# main_sch.net
KiCad netlist of a schematic drawn in Altium Designer
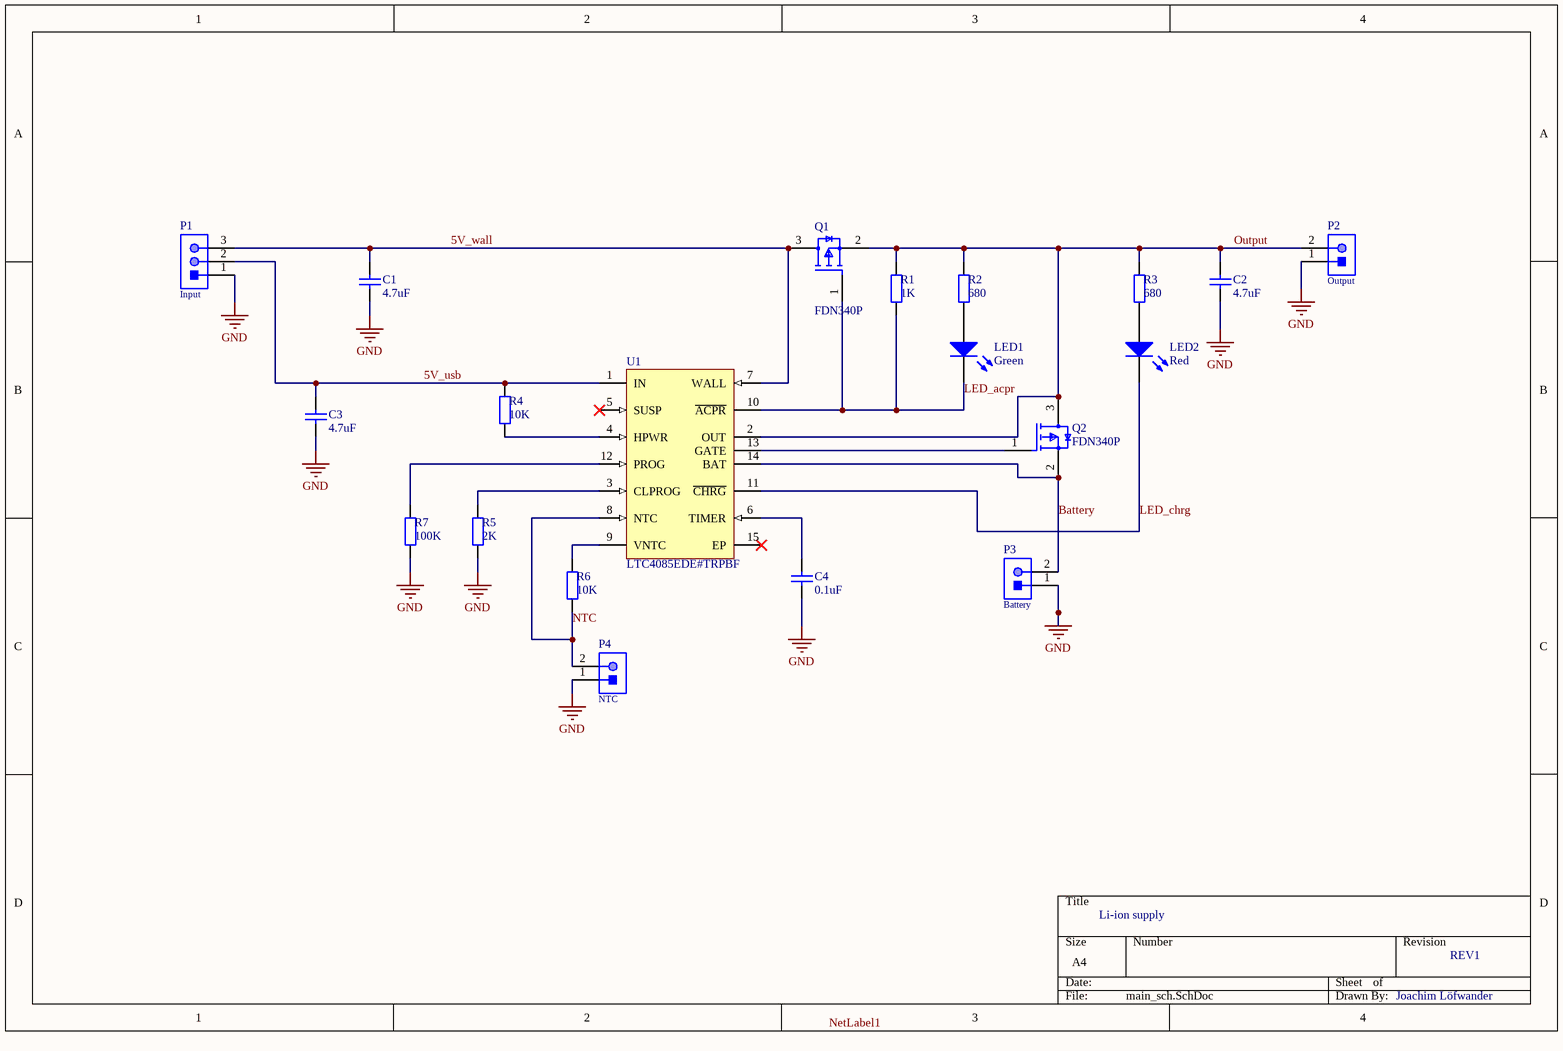
[diagram p0: main_sch.SchDoc]

(export (version "E")
  (design (tool "Eeschema 10.0.6"))
  (components
    (comp (ref "C1")
      (value "4.7uF")
      (footprint "CAPC2013X145X50ML20T25")
      (fields (field (name "MANUFACTURER") "Kemet") (field (name "PART NUMBER") "C0805C475K3PACTU"))
      (libsource (lib "Altium Content Vault") (part "CAP"))
    )
    (comp (ref "C2")
      (value "4.7uF")
      (footprint "CAPC2013X145X50ML20T25")
      (fields (field (name "MANUFACTURER") "Kemet") (field (name "PART NUMBER") "C0805C475K3PACTU"))
      (libsource (lib "Altium Content Vault") (part "CAP"))
    )
    (comp (ref "C3")
      (value "4.7uF")
      (footprint "CAPC2013X145X50ML20T25")
      (fields (field (name "MANUFACTURER") "Kemet") (field (name "PART NUMBER") "C0805C475K3PACTU"))
      (libsource (lib "Altium Content Vault") (part "CAP"))
    )
    (comp (ref "C4")
      (value "0.1uF")
      (footprint "CAPC2013X135X45ML10T25")
      (description "Chip Capacitor, 0.1 uF, +/- 10%, 50 V, -55 to 125 degC, 0805 (2012 Metric), RoHS, Tape and Reel")
      (fields (field (name "VOLTAGE") "50V") (field (name "TOLERANCE") "10%"))
      (libsource (lib "Altium Content Vault") (part "CAP-NP-2"))
    )
    (comp (ref "LED1")
      (value "Green")
      (footprint "0805_A")
      (description "SMD mono-color Chip LED, WL-SMCW, Green")
      (fields (field (name "PARTNUMBER") "150080GS75000") (field (name "MANUFACTURER") "Wuerth Elektronik"))
      (libsource (lib "Altium Content Vault") (part "WE-LED_K1A2-2"))
    )
    (comp (ref "LED2")
      (value "Red")
      (footprint "0805_A")
      (description "SMD mono-color Chip LED, WL-SMCW, Red")
      (fields (field (name "PARTNUMBER") "150080RS75000") (field (name "MANUFACTURER") "Wuerth Elektronik"))
      (libsource (lib "Altium Content Vault") (part "WE-LED_K1A2-2"))
    )
    (comp (ref "P1")
      (value "Input")
      (footprint "61300311121")
      (description "THT Vertical Pin Header WR-PHD, Pitch 2.54 mm, Single Row, 3 pins")
      (fields
        (field (name "PART NUMBER") "61300311121")
        (field (name "MANUFACTURER") "Wurth Elektronik")
        (field (name "PUBLISHER") "WurthElektronik")
      )
      (libsource (lib "Altium Content Vault") (part "WE-CN-1P-M-R3"))
    )
    (comp (ref "P2")
      (value "Output")
      (footprint "61300211121")
      (description "THT Vertical Pin Header WR-PHD, Pitch 2.54 mm, Single Row, 2 pins")
      (fields
        (field (name "MANUFACTURER") "Wurth Elektronik")
        (field (name "PART NUMBER") "61300211121")
        (field (name "PUBLISHER") "WurthElektronik")
      )
      (libsource (lib "") (part "WE-CN-1P-M-R2_1"))
    )
    (comp (ref "P3")
      (value "Battery")
      (footprint "61300211121")
      (description "THT Vertical Pin Header WR-PHD, Pitch 2.54 mm, Single Row, 2 pins")
      (fields
        (field (name "MANUFACTURER") "Wurth Elektronik")
        (field (name "PART NUMBER") "61300211121")
        (field (name "PUBLISHER") "WurthElektronik")
      )
      (libsource (lib "Altium Content Vault") (part "WE-CN-1P-M-R2"))
    )
    (comp (ref "P4")
      (value "NTC")
      (footprint "61300211121")
      (description "THT Vertical Pin Header WR-PHD, Pitch 2.54 mm, Single Row, 2 pins")
      (fields
        (field (name "MANUFACTURER") "Wurth Elektronik")
        (field (name "PART NUMBER") "61300211121")
        (field (name "PUBLISHER") "WurthElektronik")
      )
      (libsource (lib "") (part "WE-CN-1P-M-R2_1"))
    )
    (comp (ref "Q1")
      (value "FDN340P")
      (footprint "FP-527AG-MFG")
      (description "MOSFET P-CH 20V 2A SSOT3")
      (libsource (lib "Altium Content Vault") (part "d23f43cc42f60b967b7caccf14518fd"))
    )
    (comp (ref "Q2")
      (value "FDN340P")
      (footprint "FP-527AG-MFG")
      (description "MOSFET P-CH 20V 2A SSOT3")
      (libsource (lib "Altium Content Vault") (part "d23f43cc42f60b967b7caccf14518fd"))
    )
    (comp (ref "R1")
      (value "1K")
      (footprint "RESC2013X50X30ML20T20")
      (fields (field (name "PART NUMBER") "CRCW08051K00FKEA") (field (name "MANUFACTURER") "Vishay Dale"))
      (libsource (lib "Altium Content Vault") (part "RES"))
    )
    (comp (ref "R2")
      (value "680")
      (footprint "RESC2013X50X30ML20T20")
      (fields (field (name "MANUFACTURER") "Vishay Dale") (field (name "PART NUMBER") "CRCW0805680RFKEA"))
      (libsource (lib "Altium Content Vault") (part "RES"))
    )
    (comp (ref "R3")
      (value "680")
      (footprint "RESC2013X50X30ML20T20")
      (fields (field (name "MANUFACTURER") "Vishay Dale") (field (name "PART NUMBER") "CRCW0805680RFKEA"))
      (libsource (lib "Altium Content Vault") (part "RES"))
    )
    (comp (ref "R4")
      (value "10K")
      (footprint "RESC2013X70X40ML20T20")
      (fields (field (name "PART NUMBER") "ERJ-6GEYJ103V") (field (name "MANUFACTURER") "Panasonic"))
      (libsource (lib "Altium Content Vault") (part "RES"))
    )
    (comp (ref "R5")
      (value "2K")
      (footprint "RESC2013X60X35ML10T20")
      (fields (field (name "MANUFACTURER") "Yageo") (field (name "PART NUMBER") "RC0805JR-072KL"))
      (libsource (lib "Altium Content Vault") (part "RES"))
    )
    (comp (ref "R6")
      (value "10K")
      (footprint "RESC2012X145X30ML20T15")
      (fields (field (name "MANUFACTURER") "Vishay Dale") (field (name "PART NUMBER") "NTHS0805N02N1002JE"))
      (libsource (lib "Altium Content Vault") (part "RES"))
    )
    (comp (ref "R7")
      (value "100K")
      (footprint "RESC2013X70X40ML20T20")
      (fields (field (name "PART NUMBER") "ERJ-6GEYJ104V") (field (name "MANUFACTURER") "Panasonic"))
      (libsource (lib "Altium Content Vault") (part "RES"))
    )
    (comp (ref "U1")
      (value "LTC4085EDE#TRPBF")
      (footprint "LT-DE-14_V")
      (fields (field (name "MANUFACTURER") "Linear Technology"))
      (libsource (lib "Altium Content Vault") (part "LT-LTC4085-DE-14"))
    )
  )
  (nets
    (net (code "1") (name "/5V_usb") (class "Default")
      (node (ref "C3") (pin "2") (pinfunction "2_2") (pintype "passive"))
      (node (ref "P1") (pin "2") (pinfunction "2_2") (pintype "passive"))
      (node (ref "R4") (pin "2") (pinfunction "2_2") (pintype "passive"))
      (node (ref "U1") (pin "1") (pinfunction "IN_1") (pintype "power_in"))
    )
    (net (code "2") (name "/5V_wall") (class "Default")
      (node (ref "C1") (pin "2") (pinfunction "2_2") (pintype "passive"))
      (node (ref "P1") (pin "3") (pinfunction "3_3") (pintype "passive"))
      (node (ref "Q1") (pin "3") (pinfunction "D_3") (pintype "passive"))
      (node (ref "U1") (pin "7") (pinfunction "WALL_7") (pintype "input"))
    )
    (net (code "3") (name "/Battery") (class "Default")
      (node (ref "P3") (pin "2") (pinfunction "2_2") (pintype "passive"))
      (node (ref "Q2") (pin "2") (pinfunction "S_2") (pintype "passive"))
      (node (ref "U1") (pin "14") (pinfunction "BAT_14") (pintype "power_in"))
    )
    (net (code "4") (name "/LED_acpr") (class "Default")
      (node (ref "LED1") (pin "1") (pinfunction "K_1") (pintype "passive"))
      (node (ref "Q1") (pin "1") (pinfunction "G_1") (pintype "passive"))
      (node (ref "R1") (pin "1") (pinfunction "1_1") (pintype "passive"))
      (node (ref "U1") (pin "10") (pinfunction "~{ACPR}_10") (pintype "tri_state"))
    )
    (net (code "5") (name "/LED_chrg") (class "Default")
      (node (ref "LED2") (pin "1") (pinfunction "K_1") (pintype "passive"))
      (node (ref "U1") (pin "11") (pinfunction "~{CHRG}_11") (pintype "tri_state"))
    )
    (net (code "6") (name "/NTC") (class "Default")
      (node (ref "P4") (pin "2") (pinfunction "2_2") (pintype "passive"))
      (node (ref "R6") (pin "1") (pinfunction "1_1") (pintype "passive"))
      (node (ref "U1") (pin "8") (pinfunction "NTC_8") (pintype "input"))
    )
    (net (code "8") (name "/Output") (class "Default")
      (node (ref "C2") (pin "2") (pinfunction "2_2") (pintype "passive"))
      (node (ref "P2") (pin "2") (pinfunction "2_2") (pintype "passive"))
      (node (ref "Q1") (pin "2") (pinfunction "S_2") (pintype "passive"))
      (node (ref "Q2") (pin "3") (pinfunction "D_3") (pintype "passive"))
      (node (ref "R1") (pin "2") (pinfunction "2_2") (pintype "passive"))
      (node (ref "R2") (pin "2") (pinfunction "2_2") (pintype "passive"))
      (node (ref "R3") (pin "2") (pinfunction "2_2") (pintype "passive"))
      (node (ref "U1") (pin "2") (pinfunction "OUT_2") (pintype "power_in"))
    )
    (net (code "9") (name "GND") (class "Default")
      (node (ref "C1") (pin "1") (pinfunction "1_1") (pintype "passive"))
      (node (ref "C2") (pin "1") (pinfunction "1_1") (pintype "passive"))
      (node (ref "C3") (pin "1") (pinfunction "1_1") (pintype "passive"))
      (node (ref "C4") (pin "1") (pinfunction "1_1") (pintype "passive"))
      (node (ref "P1") (pin "1") (pinfunction "1_1") (pintype "passive"))
      (node (ref "P2") (pin "1") (pinfunction "1_1") (pintype "passive"))
      (node (ref "P3") (pin "1") (pinfunction "1_1") (pintype "passive"))
      (node (ref "P4") (pin "1") (pinfunction "1_1") (pintype "passive"))
      (node (ref "R5") (pin "1") (pinfunction "1_1") (pintype "passive"))
      (node (ref "R7") (pin "1") (pinfunction "1_1") (pintype "passive"))
    )
    (net (code "10") (name "Net-(LED1-A)") (class "Default")
      (node (ref "LED1") (pin "2") (pinfunction "A_2") (pintype "passive"))
      (node (ref "R2") (pin "1") (pinfunction "1_1") (pintype "passive"))
    )
    (net (code "11") (name "Net-(LED2-A)") (class "Default")
      (node (ref "LED2") (pin "2") (pinfunction "A_2") (pintype "passive"))
      (node (ref "R3") (pin "1") (pinfunction "1_1") (pintype "passive"))
    )
    (net (code "12") (name "Net-(Q2-G)") (class "Default")
      (node (ref "Q2") (pin "1") (pinfunction "G_1") (pintype "passive"))
      (node (ref "U1") (pin "13") (pinfunction "GATE_13") (pintype "tri_state"))
    )
    (net (code "13") (name "Net-(U1-CLPROG)") (class "Default")
      (node (ref "R5") (pin "2") (pinfunction "2_2") (pintype "passive"))
      (node (ref "U1") (pin "3") (pinfunction "CLPROG_3") (pintype "input"))
    )
    (net (code "14") (name "Net-(U1-HPWR)") (class "Default")
      (node (ref "R4") (pin "1") (pinfunction "1_1") (pintype "passive"))
      (node (ref "U1") (pin "4") (pinfunction "HPWR_4") (pintype "input"))
    )
    (net (code "15") (name "Net-(U1-PROG)") (class "Default")
      (node (ref "R7") (pin "2") (pinfunction "2_2") (pintype "passive"))
      (node (ref "U1") (pin "12") (pinfunction "PROG_12") (pintype "input"))
    )
    (net (code "16") (name "Net-(U1-TIMER)") (class "Default")
      (node (ref "C4") (pin "2") (pinfunction "2_2") (pintype "passive"))
      (node (ref "U1") (pin "6") (pinfunction "TIMER_6") (pintype "input"))
    )
    (net (code "17") (name "Net-(U1-VNTC)") (class "Default")
      (node (ref "R6") (pin "2") (pinfunction "2_2") (pintype "passive"))
      (node (ref "U1") (pin "9") (pinfunction "VNTC_9") (pintype "passive"))
    )
    (net (code "18") (name "unconnected-(U1-EP-Pad15)") (class "Default")
      (node (ref "U1") (pin "15") (pinfunction "EP_15") (pintype "power_in+no_connect"))
    )
    (net (code "19") (name "unconnected-(U1-SUSP-Pad5)") (class "Default")
      (node (ref "U1") (pin "5") (pinfunction "SUSP_5") (pintype "input+no_connect"))
    )
  )
)
